# CC_CR_CP_Mode.net
KiCad netlist of a schematic drawn in Altium Designer
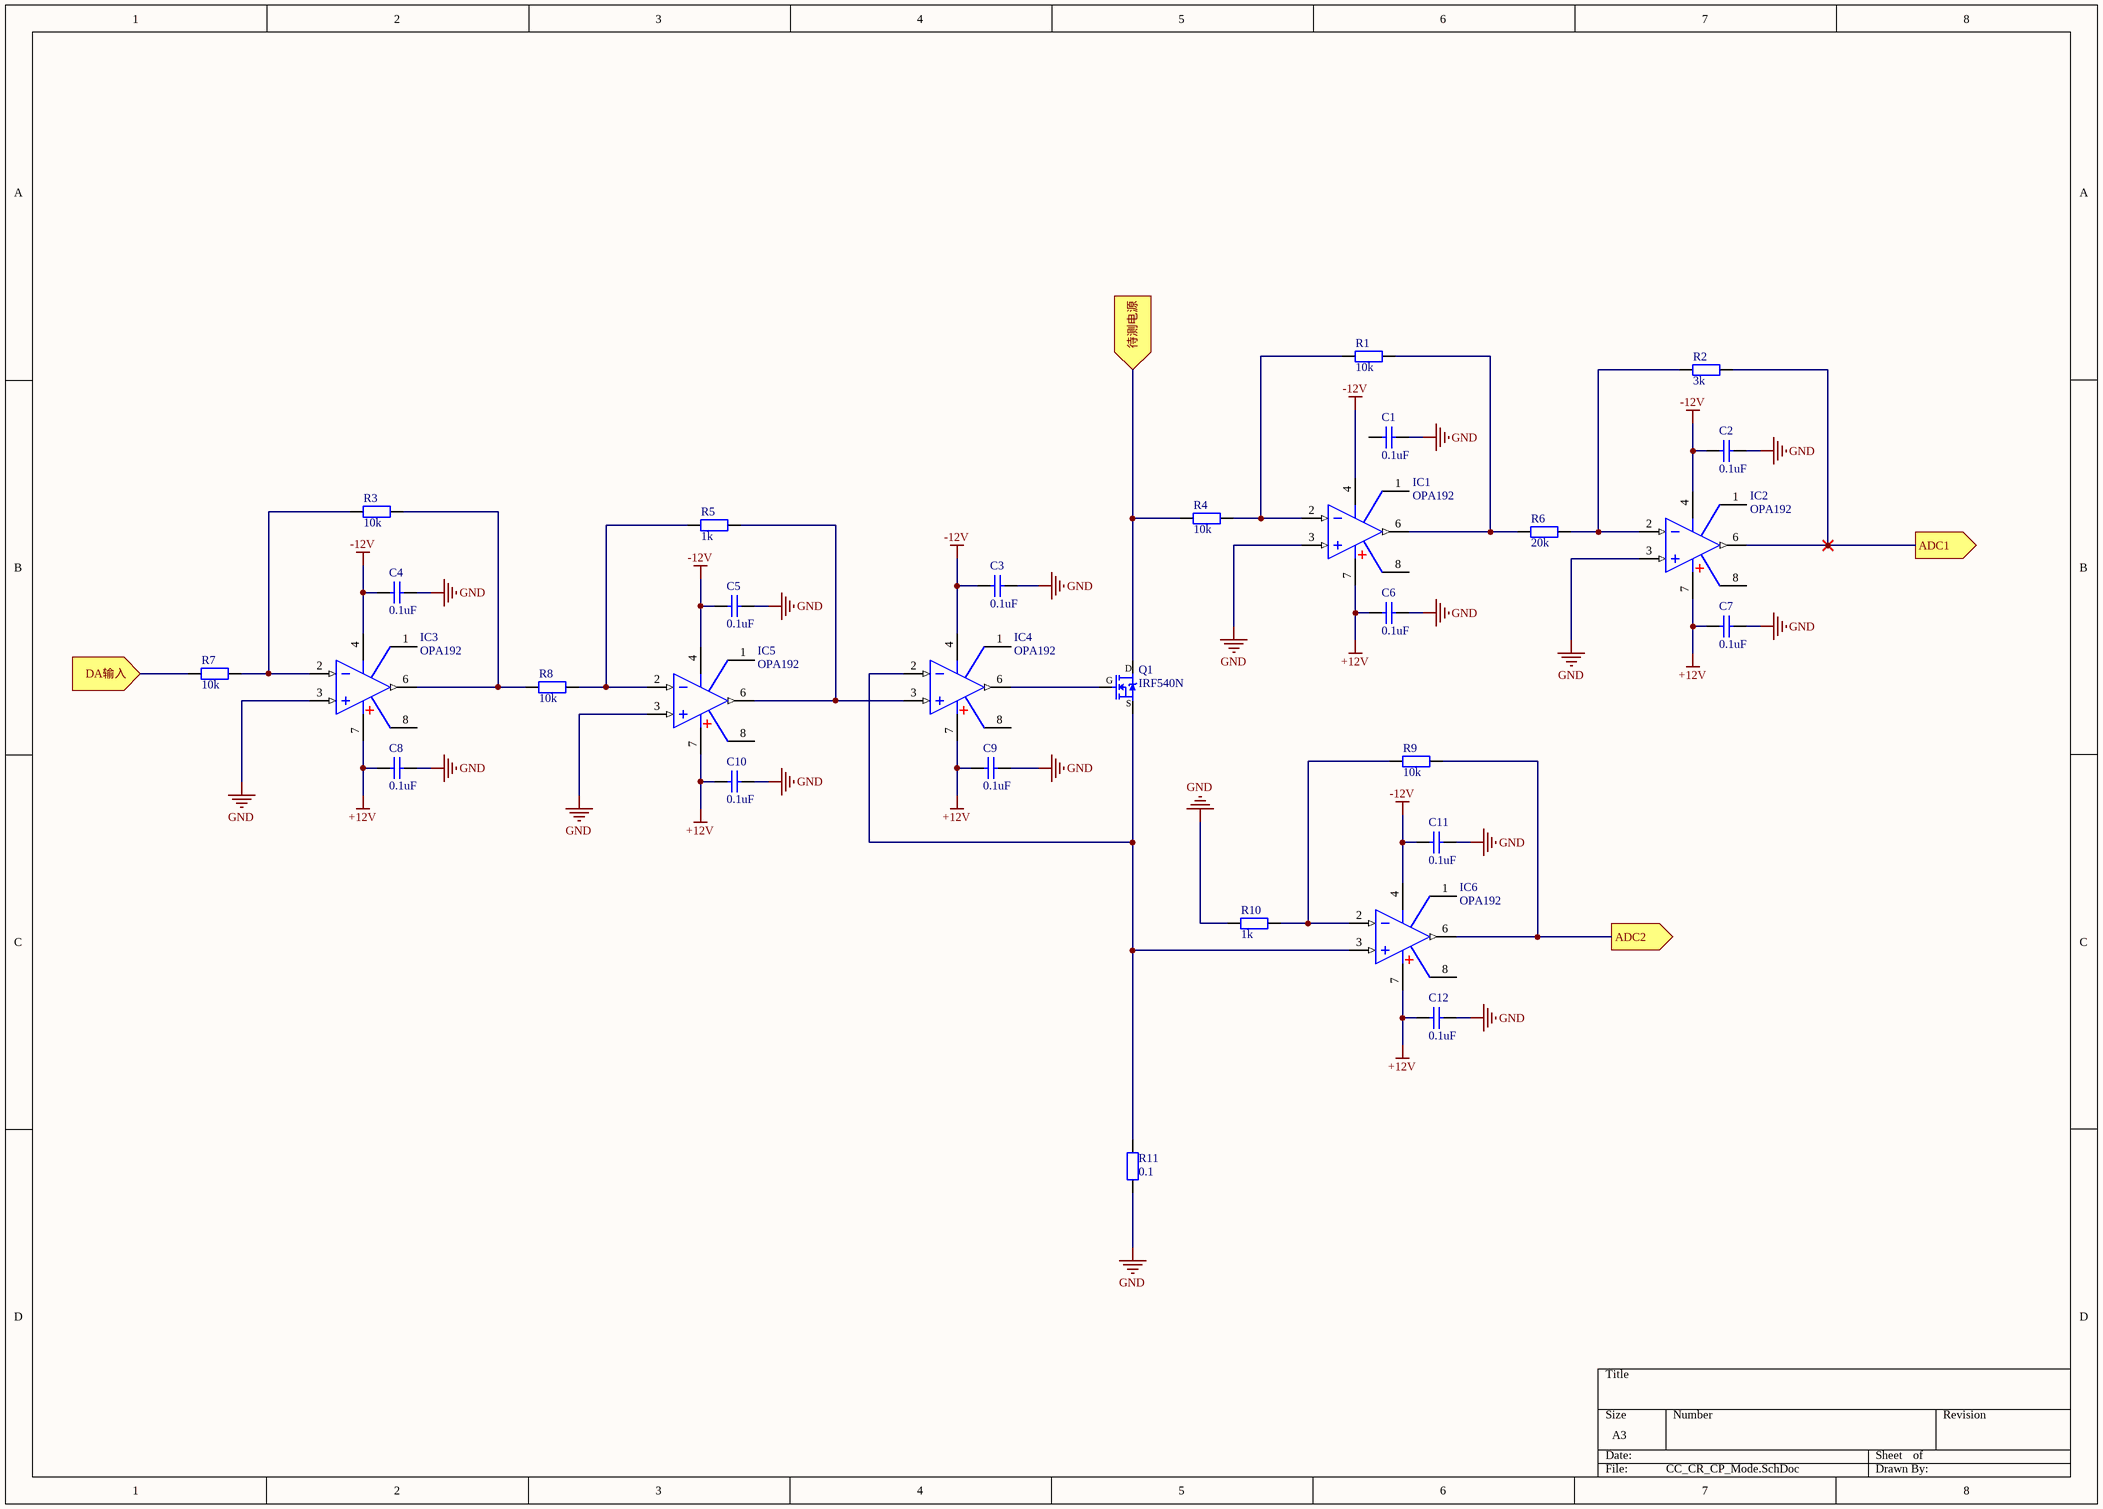
[diagram p0: CC_CR_CP_Mode.SchDoc]

(export (version "E")
  (design (tool "Eeschema 10.0.6"))
  (components
    (comp (ref "C1")
      (value "0.1uF")
      (footprint "瓷片电容")
      (description "直插电容")
      (fields (field (name "VOLTAGE") "63V") (field (name "PUBLISHER") "Altium Limited"))
      (libsource (lib "My_Intlib") (part "Cap_DIP"))
    )
    (comp (ref "C2")
      (value "0.1uF")
      (footprint "瓷片电容")
      (description "直插电容")
      (fields (field (name "VOLTAGE") "63V") (field (name "PUBLISHER") "Altium Limited"))
      (libsource (lib "My_Intlib") (part "Cap_DIP"))
    )
    (comp (ref "C3")
      (value "0.1uF")
      (footprint "瓷片电容")
      (description "直插电容")
      (fields (field (name "VOLTAGE") "63V") (field (name "PUBLISHER") "Altium Limited"))
      (libsource (lib "My_Intlib") (part "Cap_DIP"))
    )
    (comp (ref "C4")
      (value "0.1uF")
      (footprint "瓷片电容")
      (description "直插电容")
      (fields (field (name "VOLTAGE") "63V") (field (name "PUBLISHER") "Altium Limited"))
      (libsource (lib "My_Intlib") (part "Cap_DIP"))
    )
    (comp (ref "C5")
      (value "0.1uF")
      (footprint "瓷片电容")
      (description "直插电容")
      (fields (field (name "VOLTAGE") "63V") (field (name "PUBLISHER") "Altium Limited"))
      (libsource (lib "My_Intlib") (part "Cap_DIP"))
    )
    (comp (ref "C6")
      (value "0.1uF")
      (footprint "瓷片电容")
      (description "直插电容")
      (fields (field (name "VOLTAGE") "63V") (field (name "PUBLISHER") "Altium Limited"))
      (libsource (lib "My_Intlib") (part "Cap_DIP"))
    )
    (comp (ref "C7")
      (value "0.1uF")
      (footprint "瓷片电容")
      (description "直插电容")
      (fields (field (name "VOLTAGE") "63V") (field (name "PUBLISHER") "Altium Limited"))
      (libsource (lib "My_Intlib") (part "Cap_DIP"))
    )
    (comp (ref "C8")
      (value "0.1uF")
      (footprint "瓷片电容")
      (description "直插电容")
      (fields (field (name "VOLTAGE") "63V") (field (name "PUBLISHER") "Altium Limited"))
      (libsource (lib "My_Intlib") (part "Cap_DIP"))
    )
    (comp (ref "C9")
      (value "0.1uF")
      (footprint "瓷片电容")
      (description "直插电容")
      (fields (field (name "VOLTAGE") "63V") (field (name "PUBLISHER") "Altium Limited"))
      (libsource (lib "My_Intlib") (part "Cap_DIP"))
    )
    (comp (ref "C10")
      (value "0.1uF")
      (footprint "瓷片电容")
      (description "直插电容")
      (fields (field (name "VOLTAGE") "63V") (field (name "PUBLISHER") "Altium Limited"))
      (libsource (lib "My_Intlib") (part "Cap_DIP"))
    )
    (comp (ref "C11")
      (value "0.1uF")
      (footprint "瓷片电容")
      (description "直插电容")
      (fields (field (name "VOLTAGE") "63V") (field (name "PUBLISHER") "Altium Limited"))
      (libsource (lib "My_Intlib") (part "Cap_DIP"))
    )
    (comp (ref "C12")
      (value "0.1uF")
      (footprint "瓷片电容")
      (description "直插电容")
      (fields (field (name "VOLTAGE") "63V") (field (name "PUBLISHER") "Altium Limited"))
      (libsource (lib "My_Intlib") (part "Cap_DIP"))
    )
    (comp (ref "IC1")
      (value "OPA192")
      (footprint "SOP8_N")
      (description "High-Voltage, Rail-to-Rail Input/Output, 5µV, 0.2µV/˚C, Precision Operational Amplifier")
      (fields (field (name "版权归属") "源创客"))
      (libsource (lib "My_Intlib") (part "OPA192"))
    )
    (comp (ref "IC2")
      (value "OPA192")
      (footprint "SOP8_N")
      (description "High-Voltage, Rail-to-Rail Input/Output, 5µV, 0.2µV/˚C, Precision Operational Amplifier")
      (fields (field (name "版权归属") "源创客"))
      (libsource (lib "My_Intlib") (part "OPA192"))
    )
    (comp (ref "IC3")
      (value "OPA192")
      (footprint "SOP8_N")
      (description "High-Voltage, Rail-to-Rail Input/Output, 5µV, 0.2µV/˚C, Precision Operational Amplifier")
      (fields (field (name "版权归属") "源创客"))
      (libsource (lib "My_Intlib") (part "OPA192"))
    )
    (comp (ref "IC4")
      (value "OPA192")
      (footprint "SOP8_N")
      (description "High-Voltage, Rail-to-Rail Input/Output, 5µV, 0.2µV/˚C, Precision Operational Amplifier")
      (fields (field (name "版权归属") "源创客"))
      (libsource (lib "My_Intlib") (part "OPA192"))
    )
    (comp (ref "IC5")
      (value "OPA192")
      (footprint "SOP8_N")
      (description "High-Voltage, Rail-to-Rail Input/Output, 5µV, 0.2µV/˚C, Precision Operational Amplifier")
      (fields (field (name "版权归属") "源创客"))
      (libsource (lib "My_Intlib") (part "OPA192"))
    )
    (comp (ref "IC6")
      (value "OPA192")
      (footprint "SOP8_N")
      (description "High-Voltage, Rail-to-Rail Input/Output, 5µV, 0.2µV/˚C, Precision Operational Amplifier")
      (fields (field (name "版权归属") "源创客"))
      (libsource (lib "My_Intlib") (part "OPA192"))
    )
    (comp (ref "Q1")
      (value "IRF540N")
      (footprint "TO263-3B")
      (description "N沟场 100V/22A")
      (fields (field (name "版权归属") "源创客"))
      (libsource (lib "My_Intlib") (part "IRF540N"))
    )
    (comp (ref "R1")
      (value "10k")
      (footprint "RS 1/4W")
      (description "直插电阻")
      (libsource (lib "My_Intlib") (part "Res_DIP"))
    )
    (comp (ref "R2")
      (value "3k")
      (footprint "RS 1/4W")
      (description "直插电阻")
      (libsource (lib "My_Intlib") (part "Res_DIP"))
    )
    (comp (ref "R3")
      (value "10k")
      (footprint "RS 1/4W")
      (description "直插电阻")
      (libsource (lib "My_Intlib") (part "Res_DIP"))
    )
    (comp (ref "R4")
      (value "10k")
      (footprint "RS 1/4W")
      (description "直插电阻")
      (libsource (lib "My_Intlib") (part "Res_DIP"))
    )
    (comp (ref "R5")
      (value "1k")
      (footprint "RS 1/4W")
      (description "直插电阻")
      (libsource (lib "My_Intlib") (part "Res_DIP"))
    )
    (comp (ref "R6")
      (value "20k")
      (footprint "RS 1/4W")
      (description "直插电阻")
      (libsource (lib "My_Intlib") (part "Res_DIP"))
    )
    (comp (ref "R7")
      (value "10k")
      (footprint "RS 1/4W")
      (description "直插电阻")
      (libsource (lib "My_Intlib") (part "Res_DIP"))
    )
    (comp (ref "R8")
      (value "10k")
      (footprint "RS 1/4W")
      (description "直插电阻")
      (libsource (lib "My_Intlib") (part "Res_DIP"))
    )
    (comp (ref "R9")
      (value "10k")
      (footprint "RS 1/4W")
      (description "直插电阻")
      (libsource (lib "My_Intlib") (part "Res_DIP"))
    )
    (comp (ref "R10")
      (value "1k")
      (footprint "RS 1/4W")
      (description "直插电阻")
      (libsource (lib "My_Intlib") (part "Res_DIP"))
    )
    (comp (ref "R11")
      (value "0.1")
      (footprint "RS 1/4W")
      (description "直插电阻")
      (libsource (lib "") (part "Res_DIP_1"))
    )
  )
  (nets
    (net (code "1") (name "+12V") (class "Default")
      (node (ref "C10") (pin "1") (pinfunction "1_1") (pintype "passive"))
      (node (ref "C12") (pin "1") (pinfunction "1_1") (pintype "passive"))
      (node (ref "C6") (pin "1") (pinfunction "1_1") (pintype "passive"))
      (node (ref "C7") (pin "1") (pinfunction "1_1") (pintype "passive"))
      (node (ref "C8") (pin "1") (pinfunction "1_1") (pintype "passive"))
      (node (ref "C9") (pin "1") (pinfunction "1_1") (pintype "passive"))
      (node (ref "IC1") (pin "7") (pinfunction "V+_7") (pintype "power_in"))
      (node (ref "IC2") (pin "7") (pinfunction "V+_7") (pintype "power_in"))
      (node (ref "IC3") (pin "7") (pinfunction "V+_7") (pintype "power_in"))
      (node (ref "IC4") (pin "7") (pinfunction "V+_7") (pintype "power_in"))
      (node (ref "IC5") (pin "7") (pinfunction "V+_7") (pintype "power_in"))
      (node (ref "IC6") (pin "7") (pinfunction "V+_7") (pintype "power_in"))
    )
    (net (code "2") (name "-12V") (class "Default")
      (node (ref "C11") (pin "1") (pinfunction "1_1") (pintype "passive"))
      (node (ref "C2") (pin "1") (pinfunction "1_1") (pintype "passive"))
      (node (ref "C3") (pin "1") (pinfunction "1_1") (pintype "passive"))
      (node (ref "C4") (pin "1") (pinfunction "1_1") (pintype "passive"))
      (node (ref "C5") (pin "1") (pinfunction "1_1") (pintype "passive"))
      (node (ref "IC1") (pin "4") (pinfunction "V-_4") (pintype "power_in"))
      (node (ref "IC2") (pin "4") (pinfunction "V-_4") (pintype "power_in"))
      (node (ref "IC3") (pin "4") (pinfunction "V-_4") (pintype "power_in"))
      (node (ref "IC4") (pin "4") (pinfunction "V-_4") (pintype "power_in"))
      (node (ref "IC5") (pin "4") (pinfunction "V-_4") (pintype "power_in"))
      (node (ref "IC6") (pin "4") (pinfunction "V-_4") (pintype "power_in"))
    )
    (net (code "3") (name "/ADC1") (class "Default")
      (node (ref "IC2") (pin "6") (pinfunction "OUT_6") (pintype "output"))
      (node (ref "R2") (pin "2") (pinfunction "2_2") (pintype "passive"))
    )
    (net (code "4") (name "/ADC2") (class "Default")
      (node (ref "IC6") (pin "6") (pinfunction "OUT_6") (pintype "output"))
      (node (ref "R9") (pin "2") (pinfunction "2_2") (pintype "passive"))
    )
    (net (code "5") (name "/DA输入") (class "Default")
      (node (ref "R7") (pin "1") (pinfunction "1_1") (pintype "passive"))
    )
    (net (code "6") (name "/待测电源") (class "Default")
      (node (ref "Q1") (pin "2") (pinfunction "S_2") (pintype "passive"))
      (node (ref "R4") (pin "1") (pinfunction "1_1") (pintype "passive"))
    )
    (net (code "7") (name "GND") (class "Default")
      (node (ref "C1") (pin "2") (pinfunction "2_2") (pintype "passive"))
      (node (ref "C10") (pin "2") (pinfunction "2_2") (pintype "passive"))
      (node (ref "C11") (pin "2") (pinfunction "2_2") (pintype "passive"))
      (node (ref "C12") (pin "2") (pinfunction "2_2") (pintype "passive"))
      (node (ref "C2") (pin "2") (pinfunction "2_2") (pintype "passive"))
      (node (ref "C3") (pin "2") (pinfunction "2_2") (pintype "passive"))
      (node (ref "C4") (pin "2") (pinfunction "2_2") (pintype "passive"))
      (node (ref "C5") (pin "2") (pinfunction "2_2") (pintype "passive"))
      (node (ref "C6") (pin "2") (pinfunction "2_2") (pintype "passive"))
      (node (ref "C7") (pin "2") (pinfunction "2_2") (pintype "passive"))
      (node (ref "C8") (pin "2") (pinfunction "2_2") (pintype "passive"))
      (node (ref "C9") (pin "2") (pinfunction "2_2") (pintype "passive"))
      (node (ref "IC1") (pin "3") (pinfunction "IN+_3") (pintype "input"))
      (node (ref "IC2") (pin "3") (pinfunction "IN+_3") (pintype "input"))
      (node (ref "IC3") (pin "3") (pinfunction "IN+_3") (pintype "input"))
      (node (ref "IC5") (pin "3") (pinfunction "IN+_3") (pintype "input"))
      (node (ref "R10") (pin "1") (pinfunction "1_1") (pintype "passive"))
      (node (ref "R11") (pin "1") (pinfunction "1_1") (pintype "passive"))
    )
    (net (code "8") (name "Net-(IC1-IN-)") (class "Default")
      (node (ref "IC1") (pin "2") (pinfunction "IN-_2") (pintype "input"))
      (node (ref "R1") (pin "1") (pinfunction "1_1") (pintype "passive"))
      (node (ref "R4") (pin "2") (pinfunction "2_2") (pintype "passive"))
    )
    (net (code "9") (name "Net-(IC1-OUT)") (class "Default")
      (node (ref "IC1") (pin "6") (pinfunction "OUT_6") (pintype "output"))
      (node (ref "R1") (pin "2") (pinfunction "2_2") (pintype "passive"))
      (node (ref "R6") (pin "1") (pinfunction "1_1") (pintype "passive"))
    )
    (net (code "10") (name "Net-(IC2-IN-)") (class "Default")
      (node (ref "IC2") (pin "2") (pinfunction "IN-_2") (pintype "input"))
      (node (ref "R2") (pin "1") (pinfunction "1_1") (pintype "passive"))
      (node (ref "R6") (pin "2") (pinfunction "2_2") (pintype "passive"))
    )
    (net (code "11") (name "Net-(IC3-IN-)") (class "Default")
      (node (ref "IC3") (pin "2") (pinfunction "IN-_2") (pintype "input"))
      (node (ref "R3") (pin "1") (pinfunction "1_1") (pintype "passive"))
      (node (ref "R7") (pin "2") (pinfunction "2_2") (pintype "passive"))
    )
    (net (code "12") (name "Net-(IC3-OUT)") (class "Default")
      (node (ref "IC3") (pin "6") (pinfunction "OUT_6") (pintype "output"))
      (node (ref "R3") (pin "2") (pinfunction "2_2") (pintype "passive"))
      (node (ref "R8") (pin "1") (pinfunction "1_1") (pintype "passive"))
    )
    (net (code "13") (name "Net-(IC4-IN+)") (class "Default")
      (node (ref "IC4") (pin "3") (pinfunction "IN+_3") (pintype "input"))
      (node (ref "IC5") (pin "6") (pinfunction "OUT_6") (pintype "output"))
      (node (ref "R5") (pin "2") (pinfunction "2_2") (pintype "passive"))
    )
    (net (code "14") (name "Net-(IC4-IN-)") (class "Default")
      (node (ref "IC4") (pin "2") (pinfunction "IN-_2") (pintype "input"))
      (node (ref "IC6") (pin "3") (pinfunction "IN+_3") (pintype "input"))
      (node (ref "Q1") (pin "3") (pinfunction "D_3") (pintype "passive"))
      (node (ref "R11") (pin "2") (pinfunction "2_2") (pintype "passive"))
    )
    (net (code "15") (name "Net-(IC4-OUT)") (class "Default")
      (node (ref "IC4") (pin "6") (pinfunction "OUT_6") (pintype "output"))
      (node (ref "Q1") (pin "1") (pinfunction "G_1") (pintype "passive"))
    )
    (net (code "16") (name "Net-(IC5-IN-)") (class "Default")
      (node (ref "IC5") (pin "2") (pinfunction "IN-_2") (pintype "input"))
      (node (ref "R5") (pin "1") (pinfunction "1_1") (pintype "passive"))
      (node (ref "R8") (pin "2") (pinfunction "2_2") (pintype "passive"))
    )
    (net (code "17") (name "Net-(IC6-IN-)") (class "Default")
      (node (ref "IC6") (pin "2") (pinfunction "IN-_2") (pintype "input"))
      (node (ref "R10") (pin "2") (pinfunction "2_2") (pintype "passive"))
      (node (ref "R9") (pin "1") (pinfunction "1_1") (pintype "passive"))
    )
    (net (code "18") (name "unconnected-(C1-Pad1)") (class "Default")
      (node (ref "C1") (pin "1") (pinfunction "1_1") (pintype "passive"))
    )
    (net (code "19") (name "unconnected-(IC1-Pad1)") (class "Default")
      (node (ref "IC1") (pin "1") (pinfunction "1_1") (pintype "passive"))
    )
    (net (code "20") (name "unconnected-(IC1-Pad8)") (class "Default")
      (node (ref "IC1") (pin "8") (pinfunction "8_8") (pintype "passive"))
    )
    (net (code "21") (name "unconnected-(IC2-Pad1)") (class "Default")
      (node (ref "IC2") (pin "1") (pinfunction "1_1") (pintype "passive"))
    )
    (net (code "22") (name "unconnected-(IC2-Pad8)") (class "Default")
      (node (ref "IC2") (pin "8") (pinfunction "8_8") (pintype "passive"))
    )
    (net (code "23") (name "unconnected-(IC3-Pad1)") (class "Default")
      (node (ref "IC3") (pin "1") (pinfunction "1_1") (pintype "passive"))
    )
    (net (code "24") (name "unconnected-(IC3-Pad8)") (class "Default")
      (node (ref "IC3") (pin "8") (pinfunction "8_8") (pintype "passive"))
    )
    (net (code "25") (name "unconnected-(IC4-Pad1)") (class "Default")
      (node (ref "IC4") (pin "1") (pinfunction "1_1") (pintype "passive"))
    )
    (net (code "26") (name "unconnected-(IC4-Pad8)") (class "Default")
      (node (ref "IC4") (pin "8") (pinfunction "8_8") (pintype "passive"))
    )
    (net (code "27") (name "unconnected-(IC5-Pad1)") (class "Default")
      (node (ref "IC5") (pin "1") (pinfunction "1_1") (pintype "passive"))
    )
    (net (code "28") (name "unconnected-(IC5-Pad8)") (class "Default")
      (node (ref "IC5") (pin "8") (pinfunction "8_8") (pintype "passive"))
    )
    (net (code "29") (name "unconnected-(IC6-Pad1)") (class "Default")
      (node (ref "IC6") (pin "1") (pinfunction "1_1") (pintype "passive"))
    )
    (net (code "30") (name "unconnected-(IC6-Pad8)") (class "Default")
      (node (ref "IC6") (pin "8") (pinfunction "8_8") (pintype "passive"))
    )
  )
)
